# Firefly2.net
KiCad netlist of a schematic drawn in EAGLE
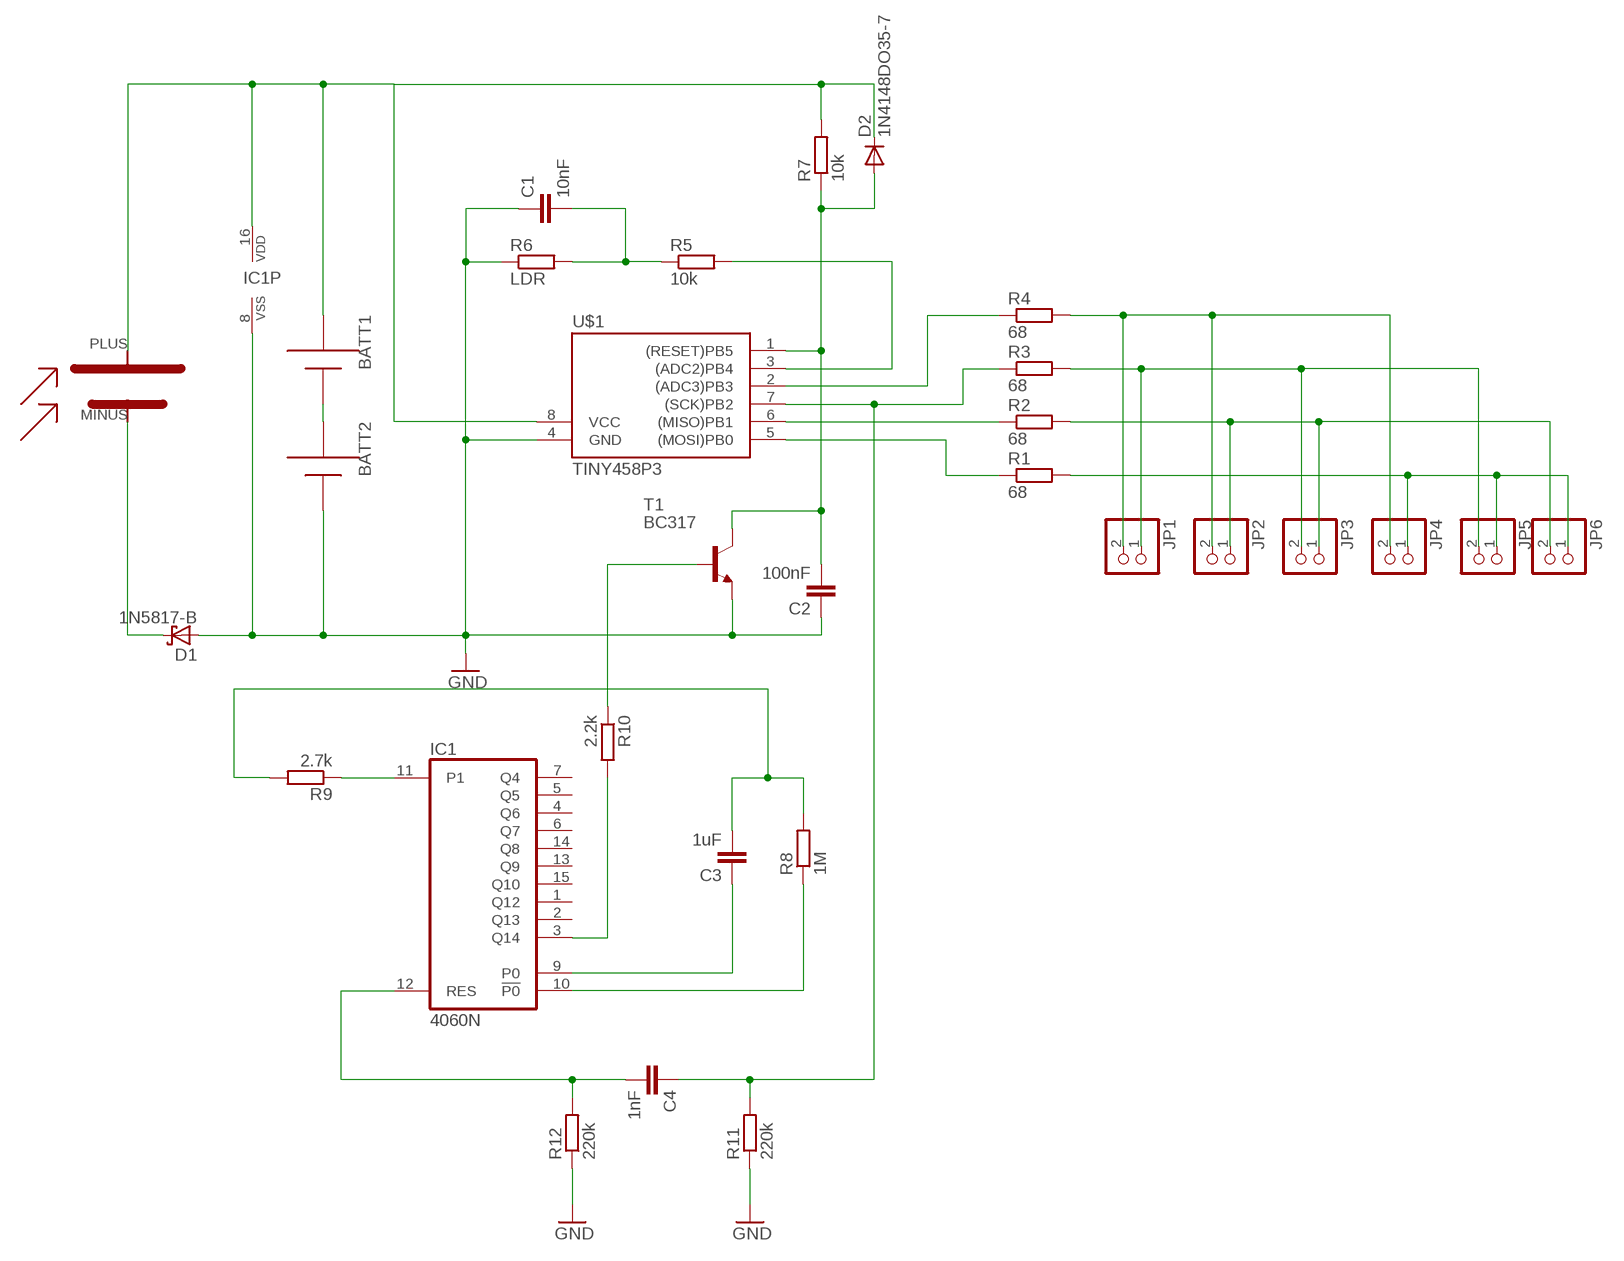
[diagram p0: schematic, sheet 1]

(export (version "E")
  (design (tool "Eeschema 10.0.6"))
  (components
    (comp (ref "BATT1")
      (value "AAA")
      (footprint "eagle-import:12BH412")
      (libsource (lib "eagle-import") (part "AAA"))
    )
    (comp (ref "BATT2")
      (value "AAA")
      (footprint "eagle-import:12BH412")
      (libsource (lib "eagle-import") (part "AAA"))
    )
    (comp (ref "C1")
      (value "10nF")
      (footprint "eagle-import:C025-025X050")
      (libsource (lib "eagle-import") (part "C-EU025-025X050"))
    )
    (comp (ref "C2")
      (value "100nF")
      (footprint "eagle-import:C075-032X103")
      (libsource (lib "eagle-import") (part "C-EU075-032X103"))
    )
    (comp (ref "C3")
      (value "1uF")
      (footprint "eagle-import:C050-024X044")
      (libsource (lib "eagle-import") (part "C-EU050-024X044"))
    )
    (comp (ref "C4")
      (value "1nF")
      (footprint "eagle-import:C050-024X044")
      (libsource (lib "eagle-import") (part "C-EU050-024X044"))
    )
    (comp (ref "D1")
      (value "1N5817-B")
      (footprint "eagle-import:DO41-7.6")
      (libsource (lib "eagle-import") (part "1N5817-B"))
    )
    (comp (ref "D2")
      (value "1N4148DO35-7")
      (footprint "eagle-import:DO35-7")
      (libsource (lib "eagle-import") (part "1N4148DO35-7"))
    )
    (comp (ref "IC1")
      (value "4060N")
      (footprint "eagle-import:DIL16")
      (libsource (lib "eagle-import") (part "4060N"))
    )
    (comp (ref "JP1")
      (value "PINHD-1X2")
      (footprint "eagle-import:1X02")
      (libsource (lib "eagle-import") (part "PINHD-1X2"))
    )
    (comp (ref "JP2")
      (value "PINHD-1X2")
      (footprint "eagle-import:1X02")
      (libsource (lib "eagle-import") (part "PINHD-1X2"))
    )
    (comp (ref "JP3")
      (value "PINHD-1X2")
      (footprint "eagle-import:1X02")
      (libsource (lib "eagle-import") (part "PINHD-1X2"))
    )
    (comp (ref "JP4")
      (value "PINHD-1X2")
      (footprint "eagle-import:1X02")
      (libsource (lib "eagle-import") (part "PINHD-1X2"))
    )
    (comp (ref "JP5")
      (value "PINHD-1X2")
      (footprint "eagle-import:1X02")
      (libsource (lib "eagle-import") (part "PINHD-1X2"))
    )
    (comp (ref "JP6")
      (value "PINHD-1X2")
      (footprint "eagle-import:1X02")
      (libsource (lib "eagle-import") (part "PINHD-1X2"))
    )
    (comp (ref "R1")
      (value "68")
      (footprint "eagle-import:0204_7")
      (libsource (lib "eagle-import") (part "R-EU_0204/7"))
    )
    (comp (ref "R2")
      (value "68")
      (footprint "eagle-import:0204_7")
      (libsource (lib "eagle-import") (part "R-EU_0204/7"))
    )
    (comp (ref "R3")
      (value "68")
      (footprint "eagle-import:0207_12")
      (libsource (lib "eagle-import") (part "R-EU_0207/12"))
    )
    (comp (ref "R4")
      (value "68")
      (footprint "eagle-import:0204_7")
      (libsource (lib "eagle-import") (part "R-EU_0204/7"))
    )
    (comp (ref "R5")
      (value "10k")
      (footprint "eagle-import:0207_10")
      (libsource (lib "eagle-import") (part "R-EU_0207/10"))
    )
    (comp (ref "R6")
      (value "LDR")
      (footprint "eagle-import:0204_7")
      (libsource (lib "eagle-import") (part "R-EU_0204/7"))
    )
    (comp (ref "R7")
      (value "10k")
      (footprint "eagle-import:0204_7")
      (libsource (lib "eagle-import") (part "R-EU_0204/7"))
    )
    (comp (ref "R8")
      (value "1M")
      (footprint "eagle-import:0204_7")
      (libsource (lib "eagle-import") (part "R-EU_0204/7"))
    )
    (comp (ref "R9")
      (value "2.7k")
      (footprint "eagle-import:0204V")
      (libsource (lib "eagle-import") (part "R-EU_0204/2V"))
    )
    (comp (ref "R10")
      (value "2.2k")
      (footprint "eagle-import:0204_7")
      (libsource (lib "eagle-import") (part "R-EU_0204/7"))
    )
    (comp (ref "R11")
      (value "220k")
      (footprint "eagle-import:0204_7")
      (libsource (lib "eagle-import") (part "R-EU_0204/7"))
    )
    (comp (ref "R12")
      (value "220k")
      (footprint "eagle-import:0204_7")
      (libsource (lib "eagle-import") (part "R-EU_0204/7"))
    )
    (comp (ref "T1")
      (value "BC317")
      (footprint "eagle-import:TO92-EBC")
      (libsource (lib "eagle-import") (part "-NPN-TO92-EBCBC317"))
    )
    (comp (ref "U$1")
      (value "TINY458P3")
      (footprint "eagle-import:DIL08")
      (libsource (lib "eagle-import") (part "TINY458P3"))
    )
    (comp (ref "U$2")
      (value "SOLARCELL4V35MACONRAD")
      (footprint "eagle-import:SOLARCELL35X39")
      (libsource (lib "eagle-import") (part "SOLARCELL4V35MACONRAD"))
    )
  )
  (nets
    (net (code "1") (name "GND") (class "Default")
      (node (ref "BATT2") (pin "-") (pinfunction "-_-") (pintype "bidirectional"))
      (node (ref "C1") (pin "1") (pinfunction "1_1") (pintype "passive"))
      (node (ref "C2") (pin "1") (pinfunction "1_1") (pintype "passive"))
      (node (ref "D1") (pin "A") (pinfunction "A_A") (pintype "passive"))
      (node (ref "IC1") (pin "8") (pinfunction "VSS_8") (pintype "power_in"))
      (node (ref "R11") (pin "1") (pinfunction "1_1") (pintype "passive"))
      (node (ref "R12") (pin "1") (pinfunction "1_1") (pintype "passive"))
      (node (ref "R6") (pin "1") (pinfunction "1_1") (pintype "passive"))
      (node (ref "T1") (pin "E") (pinfunction "E_E") (pintype "passive"))
      (node (ref "U$1") (pin "4") (pinfunction "GND_4") (pintype "power_in"))
    )
    (net (code "2") (name "Net-(BATT1-Pad-)") (class "Default")
      (node (ref "BATT1") (pin "-") (pinfunction "-_-") (pintype "bidirectional"))
      (node (ref "BATT2") (pin "+") (pinfunction "+_+") (pintype "bidirectional"))
    )
    (net (code "3") (name "Net-(C1-Pad2)") (class "Default")
      (node (ref "C1") (pin "2") (pinfunction "2_2") (pintype "passive"))
      (node (ref "R5") (pin "1") (pinfunction "1_1") (pintype "passive"))
      (node (ref "R6") (pin "2") (pinfunction "2_2") (pintype "passive"))
    )
    (net (code "4") (name "Net-(C3-Pad2)") (class "Default")
      (node (ref "C3") (pin "2") (pinfunction "2_2") (pintype "passive"))
      (node (ref "R8") (pin "2") (pinfunction "2_2") (pintype "passive"))
      (node (ref "R9") (pin "2") (pinfunction "2_2") (pintype "passive"))
    )
    (net (code "5") (name "Net-(D1-PadC)") (class "Default")
      (node (ref "D1") (pin "C") (pinfunction "C_C") (pintype "passive"))
      (node (ref "U$2") (pin "MINUS") (pinfunction "MINUS_MINUS") (pintype "power_in"))
    )
    (net (code "6") (name "Net-(IC1A-P0)") (class "Default")
      (node (ref "C3") (pin "1") (pinfunction "1_1") (pintype "passive"))
      (node (ref "IC1") (pin "9") (pinfunction "P0_9") (pintype "output"))
    )
    (net (code "7") (name "Net-(IC1A-P1)") (class "Default")
      (node (ref "IC1") (pin "11") (pinfunction "P1_11") (pintype "input"))
      (node (ref "R9") (pin "1") (pinfunction "1_1") (pintype "passive"))
    )
    (net (code "8") (name "Net-(IC1A-Q14)") (class "Default")
      (node (ref "IC1") (pin "3") (pinfunction "Q14_3") (pintype "output"))
      (node (ref "R10") (pin "2") (pinfunction "2_2") (pintype "passive"))
    )
    (net (code "9") (name "Net-(IC1A-RES)") (class "Default")
      (node (ref "C4") (pin "2") (pinfunction "2_2") (pintype "passive"))
      (node (ref "IC1") (pin "12") (pinfunction "RES_12") (pintype "input"))
      (node (ref "R12") (pin "2") (pinfunction "2_2") (pintype "passive"))
    )
    (net (code "10") (name "Net-(IC1A-~{P0})") (class "Default")
      (node (ref "IC1") (pin "10") (pinfunction "~{P0}_10") (pintype "output"))
      (node (ref "R8") (pin "1") (pinfunction "1_1") (pintype "passive"))
    )
    (net (code "11") (name "Net-(IC1B-VDD)") (class "Default")
      (node (ref "BATT1") (pin "+") (pinfunction "+_+") (pintype "bidirectional"))
      (node (ref "D2") (pin "C") (pinfunction "C_C") (pintype "passive"))
      (node (ref "IC1") (pin "16") (pinfunction "VDD_16") (pintype "power_in"))
      (node (ref "R7") (pin "2") (pinfunction "2_2") (pintype "passive"))
      (node (ref "U$1") (pin "8") (pinfunction "VCC_8") (pintype "power_in"))
      (node (ref "U$2") (pin "PLUS") (pinfunction "PLUS_PLUS") (pintype "power_in"))
    )
    (net (code "12") (name "Net-(JP1-Pad1)") (class "Default")
      (node (ref "JP1") (pin "1") (pinfunction "1_1") (pintype "passive"))
      (node (ref "JP3") (pin "2") (pinfunction "2_2") (pintype "passive"))
      (node (ref "JP5") (pin "2") (pinfunction "2_2") (pintype "passive"))
      (node (ref "R3") (pin "2") (pinfunction "2_2") (pintype "passive"))
    )
    (net (code "13") (name "Net-(JP1-Pad2)") (class "Default")
      (node (ref "JP1") (pin "2") (pinfunction "2_2") (pintype "passive"))
      (node (ref "JP2") (pin "2") (pinfunction "2_2") (pintype "passive"))
      (node (ref "JP4") (pin "2") (pinfunction "2_2") (pintype "passive"))
      (node (ref "R4") (pin "2") (pinfunction "2_2") (pintype "passive"))
    )
    (net (code "14") (name "Net-(JP2-Pad1)") (class "Default")
      (node (ref "JP2") (pin "1") (pinfunction "1_1") (pintype "passive"))
      (node (ref "JP3") (pin "1") (pinfunction "1_1") (pintype "passive"))
      (node (ref "JP6") (pin "2") (pinfunction "2_2") (pintype "passive"))
      (node (ref "R2") (pin "2") (pinfunction "2_2") (pintype "passive"))
    )
    (net (code "15") (name "Net-(JP4-Pad1)") (class "Default")
      (node (ref "JP4") (pin "1") (pinfunction "1_1") (pintype "passive"))
      (node (ref "JP5") (pin "1") (pinfunction "1_1") (pintype "passive"))
      (node (ref "JP6") (pin "1") (pinfunction "1_1") (pintype "passive"))
      (node (ref "R1") (pin "2") (pinfunction "2_2") (pintype "passive"))
    )
    (net (code "16") (name "Net-(R10-Pad1)") (class "Default")
      (node (ref "R10") (pin "1") (pinfunction "1_1") (pintype "passive"))
      (node (ref "T1") (pin "B") (pinfunction "B_B") (pintype "passive"))
    )
    (net (code "17") (name "Net-(U$1-(ADC2)PB4)") (class "Default")
      (node (ref "R5") (pin "2") (pinfunction "2_2") (pintype "passive"))
      (node (ref "U$1") (pin "3") (pinfunction "(ADC2)PB4_3") (pintype "bidirectional"))
    )
    (net (code "18") (name "Net-(U$1-(ADC3)PB3)") (class "Default")
      (node (ref "R4") (pin "1") (pinfunction "1_1") (pintype "passive"))
      (node (ref "U$1") (pin "2") (pinfunction "(ADC3)PB3_2") (pintype "bidirectional"))
    )
    (net (code "19") (name "Net-(U$1-(MISO)PB1)") (class "Default")
      (node (ref "R2") (pin "1") (pinfunction "1_1") (pintype "passive"))
      (node (ref "U$1") (pin "6") (pinfunction "(MISO)PB1_6") (pintype "bidirectional"))
    )
    (net (code "20") (name "Net-(U$1-(MOSI)PB0)") (class "Default")
      (node (ref "R1") (pin "1") (pinfunction "1_1") (pintype "passive"))
      (node (ref "U$1") (pin "5") (pinfunction "(MOSI)PB0_5") (pintype "bidirectional"))
    )
    (net (code "21") (name "Net-(U$1-(RESET)PB5)") (class "Default")
      (node (ref "C2") (pin "2") (pinfunction "2_2") (pintype "passive"))
      (node (ref "D2") (pin "A") (pinfunction "A_A") (pintype "passive"))
      (node (ref "R7") (pin "1") (pinfunction "1_1") (pintype "passive"))
      (node (ref "T1") (pin "C") (pinfunction "C_C") (pintype "passive"))
      (node (ref "U$1") (pin "1") (pinfunction "(RESET)PB5_1") (pintype "bidirectional"))
    )
    (net (code "22") (name "Net-(U$1-(SCK)PB2)") (class "Default")
      (node (ref "C4") (pin "1") (pinfunction "1_1") (pintype "passive"))
      (node (ref "R11") (pin "2") (pinfunction "2_2") (pintype "passive"))
      (node (ref "R3") (pin "1") (pinfunction "1_1") (pintype "passive"))
      (node (ref "U$1") (pin "7") (pinfunction "(SCK)PB2_7") (pintype "bidirectional"))
    )
    (net (code "23") (name "unconnected-(IC1A-Q4-Pad7)") (class "Default")
      (node (ref "IC1") (pin "7") (pinfunction "Q4_7") (pintype "output"))
    )
    (net (code "24") (name "unconnected-(IC1A-Q5-Pad5)") (class "Default")
      (node (ref "IC1") (pin "5") (pinfunction "Q5_5") (pintype "output"))
    )
    (net (code "25") (name "unconnected-(IC1A-Q6-Pad4)") (class "Default")
      (node (ref "IC1") (pin "4") (pinfunction "Q6_4") (pintype "output"))
    )
    (net (code "26") (name "unconnected-(IC1A-Q7-Pad6)") (class "Default")
      (node (ref "IC1") (pin "6") (pinfunction "Q7_6") (pintype "output"))
    )
    (net (code "27") (name "unconnected-(IC1A-Q8-Pad14)") (class "Default")
      (node (ref "IC1") (pin "14") (pinfunction "Q8_14") (pintype "output"))
    )
    (net (code "28") (name "unconnected-(IC1A-Q9-Pad13)") (class "Default")
      (node (ref "IC1") (pin "13") (pinfunction "Q9_13") (pintype "output"))
    )
    (net (code "29") (name "unconnected-(IC1A-Q10-Pad15)") (class "Default")
      (node (ref "IC1") (pin "15") (pinfunction "Q10_15") (pintype "output"))
    )
    (net (code "30") (name "unconnected-(IC1A-Q12-Pad1)") (class "Default")
      (node (ref "IC1") (pin "1") (pinfunction "Q12_1") (pintype "output"))
    )
    (net (code "31") (name "unconnected-(IC1A-Q13-Pad2)") (class "Default")
      (node (ref "IC1") (pin "2") (pinfunction "Q13_2") (pintype "output"))
    )
  )
)
